# 04_FEATHER-CONNECTION.net
KiCad netlist of a schematic drawn in Altium Designer
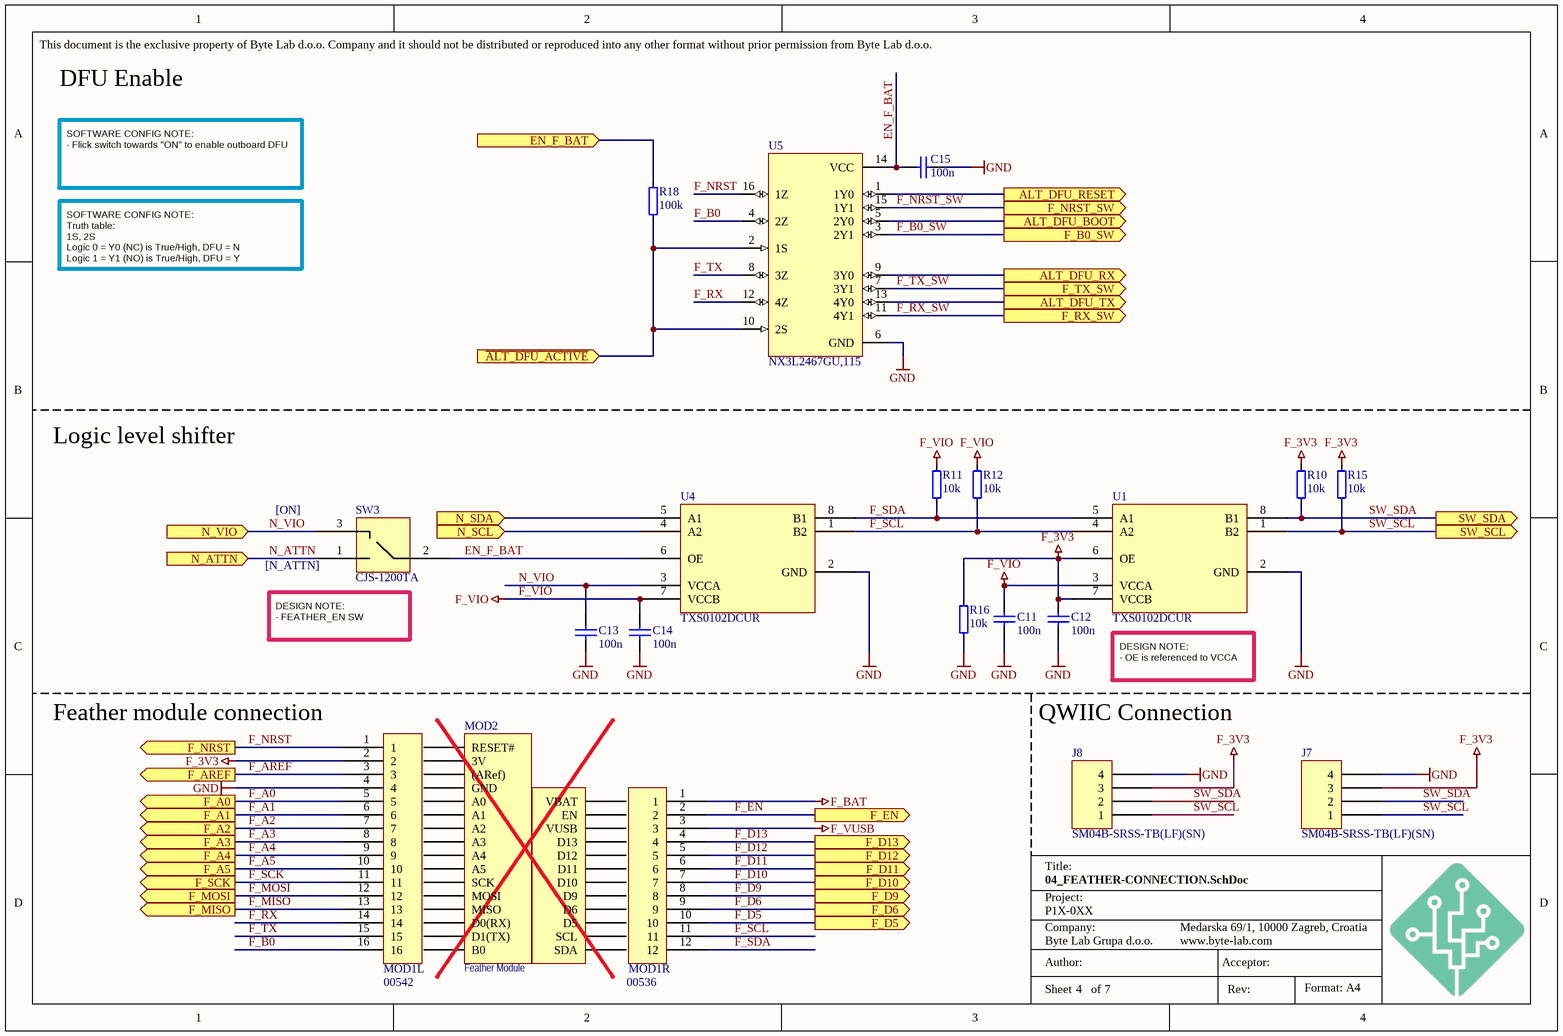
[diagram p0: 04_FEATHER-CONNECTION.SchDoc]

(export (version "E")
  (design (tool "Eeschema 10.0.6"))
  (components
    (comp (ref "C11")
      (value "100n")
      (footprint "C-0402")
      (description "Capacitor ceramic 100n ±10% X7R 16V 0402")
      (fields
        (field (name "BL PART NUMBER") "2000-908")
        (field (name "DRAWN_BY") "Puskar")
        (field (name "CHECKED_BY") "Dodig")
      )
      (libsource (lib "BL_Passive") (part "C0402-100n-16V-X7R"))
    )
    (comp (ref "C12")
      (value "100n")
      (footprint "C-0402")
      (description "Capacitor ceramic 100n ±10% X7R 16V 0402")
      (fields
        (field (name "BL PART NUMBER") "2000-908")
        (field (name "DRAWN_BY") "Puskar")
        (field (name "CHECKED_BY") "Dodig")
      )
      (libsource (lib "BL_Passive") (part "C0402-100n-16V-X7R"))
    )
    (comp (ref "C13")
      (value "100n")
      (footprint "C-0402")
      (description "Capacitor ceramic 100n ±10% X7R 16V 0402")
      (fields
        (field (name "BL PART NUMBER") "2000-908")
        (field (name "DRAWN_BY") "Puskar")
        (field (name "CHECKED_BY") "Dodig")
      )
      (libsource (lib "BL_Passive") (part "C0402-100n-16V-X7R"))
    )
    (comp (ref "C14")
      (value "100n")
      (footprint "C-0402")
      (description "Capacitor ceramic 100n ±10% X7R 16V 0402")
      (fields
        (field (name "BL PART NUMBER") "2000-908")
        (field (name "DRAWN_BY") "Puskar")
        (field (name "CHECKED_BY") "Dodig")
      )
      (libsource (lib "BL_Passive") (part "C0402-100n-16V-X7R"))
    )
    (comp (ref "C15")
      (value "100n")
      (footprint "C-0402")
      (description "Capacitor ceramic 100n ±10% X7R 16V 0402")
      (fields
        (field (name "BL PART NUMBER") "2000-908")
        (field (name "DRAWN_BY") "Puskar")
        (field (name "CHECKED_BY") "Dodig")
      )
      (libsource (lib "BL_Passive") (part "C0402-100n-16V-X7R"))
    )
    (comp (ref "J7")
      (value "SM04B-SRSS-TB(LF)(SN)")
      (footprint "JST SM04B-SRSS-TB")
      (description "CONN HEADER SH 4POS SIDE 1MM TIN")
      (fields
        (field (name "MANUFACTURER") "JST Sales America Inc.")
        (field (name "BL PART NUMBER") "2002-058")
        (field (name "DRAWN_BY") "Blues Wireless")
      )
      (libsource (lib "n21-p2") (part "SM04B-SRSS-TB(LF)(SN)"))
    )
    (comp (ref "J8")
      (value "SM04B-SRSS-TB(LF)(SN)")
      (footprint "JST SM04B-SRSS-TB")
      (description "CONN HEADER SH 4POS SIDE 1MM TIN")
      (fields
        (field (name "MANUFACTURER") "JST Sales America Inc.")
        (field (name "BL PART NUMBER") "2002-058")
        (field (name "DRAWN_BY") "Blues Wireless")
      )
      (libsource (lib "n21-p2") (part "SM04B-SRSS-TB(LF)(SN)"))
    )
    (comp (ref "MOD1L")
      (value "00542")
      (footprint "16PIN_254MM")
      (description "Socket 16-Pin, 0.100 in")
      (fields
        (field (name "MANUFACTURER") "4UCON")
        (field (name "BL PART NUMBER") "2010-423")
        (field (name "DRAWN_BY") "Blues Wireless")
      )
      (libsource (lib "n21-p2") (part "SOCKET_LFB_16"))
    )
    (comp (ref "MOD1R")
      (value "00536")
      (footprint "12PIN_254MM")
      (description "Socket 12-Pin, 0.100 in")
      (fields
        (field (name "MANUFACTURER") "4UCON")
        (field (name "BL PART NUMBER") "2010-424")
        (field (name "DRAWN_BY") "Blues Wireless")
      )
      (libsource (lib "n21-p2") (part "SOCKET_LFB_12"))
    )
    (comp (ref "MOD2")
      (value "Feather Module")
      (footprint "BLUES_WIRELESS_SWAN_2-54_HEADERS")
      (description "Typical Adafruit Feather Pinout")
      (libsource (lib "n21-p2") (part "ADAFRUIT_FEATHER_COMMON_1"))
    )
    (comp (ref "R10")
      (value "10k")
      (footprint "R-0402")
      (description "Resistor 10k ±1% 0402")
      (fields
        (field (name "BL PART NUMBER") "2000-729")
        (field (name "CHECKED_BY") "Dodig")
        (field (name "DRAWN_BY") "Puskar")
      )
      (libsource (lib "BL_Passive") (part "R0402-10k-1"))
    )
    (comp (ref "R11")
      (value "10k")
      (footprint "R-0402")
      (description "Resistor 10k ±1% 0402")
      (fields
        (field (name "BL PART NUMBER") "2000-729")
        (field (name "CHECKED_BY") "Dodig")
        (field (name "DRAWN_BY") "Puskar")
      )
      (libsource (lib "BL_Passive") (part "R0402-10k-1"))
    )
    (comp (ref "R12")
      (value "10k")
      (footprint "R-0402")
      (description "Resistor 10k ±1% 0402")
      (fields
        (field (name "BL PART NUMBER") "2000-729")
        (field (name "CHECKED_BY") "Dodig")
        (field (name "DRAWN_BY") "Puskar")
      )
      (libsource (lib "BL_Passive") (part "R0402-10k-1"))
    )
    (comp (ref "R15")
      (value "10k")
      (footprint "R-0402")
      (description "Resistor 10k ±1% 0402")
      (fields
        (field (name "BL PART NUMBER") "2000-729")
        (field (name "CHECKED_BY") "Dodig")
        (field (name "DRAWN_BY") "Puskar")
      )
      (libsource (lib "BL_Passive") (part "R0402-10k-1"))
    )
    (comp (ref "R16")
      (value "10k")
      (footprint "R-0402")
      (description "Resistor 10k ±1% 0402")
      (fields
        (field (name "BL PART NUMBER") "2000-729")
        (field (name "CHECKED_BY") "Dodig")
        (field (name "DRAWN_BY") "Puskar")
      )
      (libsource (lib "BL_Passive") (part "R0402-10k-1"))
    )
    (comp (ref "R18")
      (value "100k")
      (footprint "R-0402")
      (description "Resistor 100k ±1% 0402")
      (fields
        (field (name "BL PART NUMBER") "2000-727")
        (field (name "CHECKED_BY") "Dodig")
        (field (name "DRAWN_BY") "Puskar")
      )
      (libsource (lib "BL_Passive") (part "R0402-100k-1"))
    )
    (comp (ref "SW3")
      (value "CJS-1200TA")
      (footprint "SW_CJS-1200TA")
      (description "Switch Slide N.O./N.C. SPDT Raised Slide 0.1A 24VDC J-Hook SMD Embossed T/R")
      (fields
        (field (name "MANUFACTURER") "Nidec Copal")
        (field (name "BL PART NUMBER") "2007-456")
        (field (name "DRAWN_BY") "Blues Wireless")
      )
      (libsource (lib "n21-p2") (part "CJS-1200TA"))
    )
    (comp (ref "U1")
      (value "TXS0102DCUR")
      (footprint "SOP50P310X90-8N")
      (fields
        (field (name "MANUFACTURER") "Texas Instruments")
        (field (name "BL PART NUMBER") "2007-455")
        (field (name "DRAWN_BY") "Blues Wireless")
      )
      (libsource (lib "n21-p2") (part "TXS0102DCUR"))
    )
    (comp (ref "U4")
      (value "TXS0102DCUR")
      (footprint "SOP50P310X90-8N")
      (fields
        (field (name "MANUFACTURER") "Texas Instruments")
        (field (name "BL PART NUMBER") "2007-455")
        (field (name "DRAWN_BY") "Blues Wireless")
      )
      (libsource (lib "n21-p2") (part "TXS0102DCUR"))
    )
    (comp (ref "U5")
      (value "NX3L2467GU,115")
      (footprint "BL_Components:QFN40P180X260X55-16N")
      (description "IC ANALOG SWITCH DPDTX2 16XQFN")
      (fields
        (field (name "MANUFACTURER") "NXP")
        (field (name "BL PART NUMBER") "2009-148")
        (field (name "CHECKED_BY") "Duracic")
        (field (name "DRAWN_BY") "Marsic")
      )
      (libsource (lib "BL_Digital") (part "NX3L2467GU,115"))
    )
  )
  (nets
    (net (code "1") (name "/ALT_DFU_BOOT") (class "Default")
      (node (ref "U5") (pin "5") (pinfunction "2Y0_5") (pintype "bidirectional"))
    )
    (net (code "2") (name "/ALT_DFU_RESET") (class "Default")
      (node (ref "U5") (pin "1") (pinfunction "1Y0_1") (pintype "bidirectional"))
    )
    (net (code "3") (name "/ALT_DFU_RX") (class "Default")
      (node (ref "U5") (pin "9") (pinfunction "3Y0_9") (pintype "bidirectional"))
    )
    (net (code "4") (name "/ALT_DFU_TX") (class "Default")
      (node (ref "U5") (pin "13") (pinfunction "4Y0_13") (pintype "bidirectional"))
    )
    (net (code "5") (name "/EN_F_BAT") (class "Default")
      (node (ref "C15") (pin "2") (pinfunction "2_2") (pintype "passive"))
      (node (ref "R18") (pin "2") (pintype "passive"))
      (node (ref "SW3") (pin "2") (pinfunction "2_2") (pintype "passive"))
      (node (ref "U4") (pin "6") (pinfunction "OE_6") (pintype "passive"))
      (node (ref "U5") (pin "14") (pinfunction "VCC_14") (pintype "power_in"))
    )
    (net (code "6") (name "/F_A0") (class "Default")
      (node (ref "MOD1L") (pin "5") (pinfunction "5_5") (pintype "passive"))
    )
    (net (code "7") (name "/F_A1") (class "Default")
      (node (ref "MOD1L") (pin "6") (pinfunction "6_6") (pintype "passive"))
    )
    (net (code "8") (name "/F_A2") (class "Default")
      (node (ref "MOD1L") (pin "7") (pinfunction "7_7") (pintype "passive"))
    )
    (net (code "9") (name "/F_A3") (class "Default")
      (node (ref "MOD1L") (pin "8") (pinfunction "8_8") (pintype "passive"))
    )
    (net (code "10") (name "/F_A4") (class "Default")
      (node (ref "MOD1L") (pin "9") (pinfunction "9_9") (pintype "passive"))
    )
    (net (code "11") (name "/F_A5") (class "Default")
      (node (ref "MOD1L") (pin "10") (pinfunction "10_10") (pintype "passive"))
    )
    (net (code "12") (name "/F_AREF") (class "Default")
      (node (ref "MOD1L") (pin "3") (pinfunction "3_3") (pintype "passive"))
    )
    (net (code "13") (name "/F_B0") (class "Default")
      (node (ref "MOD1L") (pin "16") (pinfunction "16_16") (pintype "passive"))
      (node (ref "U5") (pin "4") (pinfunction "2Z_4") (pintype "bidirectional"))
    )
    (net (code "14") (name "/F_B0_SW") (class "Default")
      (node (ref "U5") (pin "3") (pinfunction "2Y1_3") (pintype "bidirectional"))
    )
    (net (code "15") (name "/F_D5") (class "Default")
      (node (ref "MOD1R") (pin "10") (pinfunction "10_10") (pintype "passive"))
    )
    (net (code "16") (name "/F_D6") (class "Default")
      (node (ref "MOD1R") (pin "9") (pinfunction "9_9") (pintype "passive"))
    )
    (net (code "17") (name "/F_D9") (class "Default")
      (node (ref "MOD1R") (pin "8") (pinfunction "8_8") (pintype "passive"))
    )
    (net (code "18") (name "/F_D10") (class "Default")
      (node (ref "MOD1R") (pin "7") (pinfunction "7_7") (pintype "passive"))
    )
    (net (code "19") (name "/F_D11") (class "Default")
      (node (ref "MOD1R") (pin "6") (pinfunction "6_6") (pintype "passive"))
    )
    (net (code "20") (name "/F_D12") (class "Default")
      (node (ref "MOD1R") (pin "5") (pinfunction "5_5") (pintype "passive"))
    )
    (net (code "21") (name "/F_D13") (class "Default")
      (node (ref "MOD1R") (pin "4") (pinfunction "4_4") (pintype "passive"))
    )
    (net (code "22") (name "/F_EN") (class "Default")
      (node (ref "MOD1R") (pin "2") (pinfunction "2_2") (pintype "passive"))
    )
    (net (code "23") (name "/F_MISO") (class "Default")
      (node (ref "MOD1L") (pin "13") (pinfunction "13_13") (pintype "passive"))
    )
    (net (code "24") (name "/F_MOSI") (class "Default")
      (node (ref "MOD1L") (pin "12") (pinfunction "12_12") (pintype "passive"))
    )
    (net (code "25") (name "/F_NRST") (class "Default")
      (node (ref "MOD1L") (pin "1") (pinfunction "1_1") (pintype "passive"))
      (node (ref "U5") (pin "16") (pinfunction "1Z_16") (pintype "bidirectional"))
    )
    (net (code "26") (name "/F_NRST_SW") (class "Default")
      (node (ref "U5") (pin "15") (pinfunction "1Y1_15") (pintype "bidirectional"))
    )
    (net (code "27") (name "/F_RX") (class "Default")
      (node (ref "MOD1L") (pin "14") (pinfunction "14_14") (pintype "passive"))
      (node (ref "U5") (pin "12") (pinfunction "4Z_12") (pintype "bidirectional"))
    )
    (net (code "28") (name "/F_RX_SW") (class "Default")
      (node (ref "U5") (pin "11") (pinfunction "4Y1_11") (pintype "bidirectional"))
    )
    (net (code "29") (name "/F_SCK") (class "Default")
      (node (ref "MOD1L") (pin "11") (pinfunction "11_11") (pintype "passive"))
    )
    (net (code "30") (name "/F_SCL") (class "Default")
      (node (ref "MOD1R") (pin "11") (pinfunction "11_11") (pintype "passive"))
      (node (ref "R12") (pin "1") (pintype "passive"))
      (node (ref "U1") (pin "4") (pinfunction "A2_4") (pintype "passive"))
      (node (ref "U4") (pin "1") (pinfunction "B2_1") (pintype "passive"))
    )
    (net (code "31") (name "/F_SDA") (class "Default")
      (node (ref "MOD1R") (pin "12") (pinfunction "12_12") (pintype "passive"))
      (node (ref "R11") (pin "1") (pintype "passive"))
      (node (ref "U1") (pin "5") (pinfunction "A1_5") (pintype "passive"))
      (node (ref "U4") (pin "8") (pinfunction "B1_8") (pintype "passive"))
    )
    (net (code "32") (name "/F_TX") (class "Default")
      (node (ref "MOD1L") (pin "15") (pinfunction "15_15") (pintype "passive"))
      (node (ref "U5") (pin "8") (pinfunction "3Z_8") (pintype "bidirectional"))
    )
    (net (code "33") (name "/F_TX_SW") (class "Default")
      (node (ref "U5") (pin "7") (pinfunction "3Y1_7") (pintype "bidirectional"))
    )
    (net (code "34") (name "/N_ATTN") (class "Default")
      (node (ref "SW3") (pin "1") (pinfunction "1_1") (pintype "passive"))
    )
    (net (code "35") (name "/N_SCL") (class "Default")
      (node (ref "U4") (pin "4") (pinfunction "A2_4") (pintype "passive"))
    )
    (net (code "36") (name "/N_SDA") (class "Default")
      (node (ref "U4") (pin "5") (pinfunction "A1_5") (pintype "passive"))
    )
    (net (code "37") (name "/N_VIO") (class "Default")
      (node (ref "C13") (pin "1") (pinfunction "1_1") (pintype "passive"))
      (node (ref "SW3") (pin "3") (pinfunction "3_3") (pintype "passive"))
      (node (ref "U4") (pin "3") (pinfunction "VCCA_3") (pintype "passive"))
    )
    (net (code "38") (name "/SW_SCL") (class "Default")
      (node (ref "J7") (pin "1") (pinfunction "1_1") (pintype "passive"))
      (node (ref "J8") (pin "1") (pinfunction "1_1") (pintype "passive"))
      (node (ref "R15") (pin "1") (pintype "passive"))
      (node (ref "U1") (pin "1") (pinfunction "B2_1") (pintype "passive"))
    )
    (net (code "39") (name "/SW_SDA") (class "Default")
      (node (ref "J7") (pin "2") (pinfunction "2_2") (pintype "passive"))
      (node (ref "J8") (pin "2") (pinfunction "2_2") (pintype "passive"))
      (node (ref "R10") (pin "1") (pintype "passive"))
      (node (ref "U1") (pin "8") (pinfunction "B1_8") (pintype "passive"))
    )
    (net (code "40") (name "/~{ALT_DFU_ACTIVE}") (class "Default")
      (node (ref "R18") (pin "1") (pintype "passive"))
      (node (ref "U5") (pin "10") (pinfunction "2S_10") (pintype "input"))
      (node (ref "U5") (pin "2") (pinfunction "1S_2") (pintype "input"))
    )
    (net (code "41") (name "F_3V3") (class "Default")
      (node (ref "C12") (pin "1") (pinfunction "1_1") (pintype "passive"))
      (node (ref "J7") (pin "3") (pinfunction "3_3") (pintype "passive"))
      (node (ref "J8") (pin "3") (pinfunction "3_3") (pintype "passive"))
      (node (ref "MOD1L") (pin "2") (pinfunction "2_2") (pintype "passive"))
      (node (ref "R10") (pin "2") (pintype "passive"))
      (node (ref "R15") (pin "2") (pintype "passive"))
      (node (ref "R16") (pin "1") (pintype "passive"))
      (node (ref "U1") (pin "6") (pinfunction "OE_6") (pintype "passive"))
      (node (ref "U1") (pin "7") (pinfunction "VCCB_7") (pintype "passive"))
    )
    (net (code "42") (name "F_BAT") (class "Default")
      (node (ref "MOD1R") (pin "1") (pinfunction "1_1") (pintype "passive"))
    )
    (net (code "43") (name "F_VIO") (class "Default")
      (node (ref "C11") (pin "1") (pinfunction "1_1") (pintype "passive"))
      (node (ref "C14") (pin "1") (pinfunction "1_1") (pintype "passive"))
      (node (ref "R11") (pin "2") (pintype "passive"))
      (node (ref "R12") (pin "2") (pintype "passive"))
      (node (ref "U1") (pin "3") (pinfunction "VCCA_3") (pintype "passive"))
      (node (ref "U4") (pin "7") (pinfunction "VCCB_7") (pintype "passive"))
    )
    (net (code "44") (name "F_VUSB") (class "Default")
      (node (ref "MOD1R") (pin "3") (pinfunction "3_3") (pintype "passive"))
    )
    (net (code "45") (name "GND") (class "Default")
      (node (ref "C11") (pin "2") (pinfunction "2_2") (pintype "passive"))
      (node (ref "C12") (pin "2") (pinfunction "2_2") (pintype "passive"))
      (node (ref "C13") (pin "2") (pinfunction "2_2") (pintype "passive"))
      (node (ref "C14") (pin "2") (pinfunction "2_2") (pintype "passive"))
      (node (ref "C15") (pin "1") (pinfunction "1_1") (pintype "passive"))
      (node (ref "J7") (pin "4") (pinfunction "4_4") (pintype "passive"))
      (node (ref "J8") (pin "4") (pinfunction "4_4") (pintype "passive"))
      (node (ref "MOD1L") (pin "4") (pinfunction "4_4") (pintype "passive"))
      (node (ref "R16") (pin "2") (pintype "passive"))
      (node (ref "U1") (pin "2") (pinfunction "GND_2") (pintype "passive"))
      (node (ref "U4") (pin "2") (pinfunction "GND_2") (pintype "passive"))
      (node (ref "U5") (pin "6") (pinfunction "GND_6") (pintype "power_in"))
    )
    (net (code "46") (name "unconnected-(MOD2-(ARef)-Pad3)") (class "Default")
      (node (ref "MOD2") (pin "3") (pinfunction "(ARef)_3") (pintype "passive"))
    )
    (net (code "47") (name "unconnected-(MOD2-3V-Pad2)") (class "Default")
      (node (ref "MOD2") (pin "2") (pinfunction "3V_2") (pintype "passive"))
    )
    (net (code "48") (name "unconnected-(MOD2-A0-Pad5)") (class "Default")
      (node (ref "MOD2") (pin "5") (pinfunction "A0_5") (pintype "passive"))
    )
    (net (code "49") (name "unconnected-(MOD2-A1-Pad6)") (class "Default")
      (node (ref "MOD2") (pin "6") (pinfunction "A1_6") (pintype "passive"))
    )
    (net (code "50") (name "unconnected-(MOD2-A2-Pad7)") (class "Default")
      (node (ref "MOD2") (pin "7") (pinfunction "A2_7") (pintype "passive"))
    )
    (net (code "51") (name "unconnected-(MOD2-A3-Pad8)") (class "Default")
      (node (ref "MOD2") (pin "8") (pinfunction "A3_8") (pintype "passive"))
    )
    (net (code "52") (name "unconnected-(MOD2-A4-Pad9)") (class "Default")
      (node (ref "MOD2") (pin "9") (pinfunction "A4_9") (pintype "passive"))
    )
    (net (code "53") (name "unconnected-(MOD2-A5-Pad10)") (class "Default")
      (node (ref "MOD2") (pin "10") (pinfunction "A5_10") (pintype "passive"))
    )
    (net (code "54") (name "unconnected-(MOD2-B0-Pad16)") (class "Default")
      (node (ref "MOD2") (pin "16") (pinfunction "B0_16") (pintype "passive"))
    )
    (net (code "55") (name "unconnected-(MOD2-D0(RX)-Pad14)") (class "Default")
      (node (ref "MOD2") (pin "14") (pinfunction "D0(RX)_14") (pintype "passive"))
    )
    (net (code "56") (name "unconnected-(MOD2-D1(TX)-Pad15)") (class "Default")
      (node (ref "MOD2") (pin "15") (pinfunction "D1(TX)_15") (pintype "passive"))
    )
    (net (code "57") (name "unconnected-(MOD2-D5-Pad19)") (class "Default")
      (node (ref "MOD2") (pin "19") (pinfunction "D5_19") (pintype "passive"))
    )
    (net (code "58") (name "unconnected-(MOD2-D6-Pad20)") (class "Default")
      (node (ref "MOD2") (pin "20") (pinfunction "D6_20") (pintype "passive"))
    )
    (net (code "59") (name "unconnected-(MOD2-D9-Pad21)") (class "Default")
      (node (ref "MOD2") (pin "21") (pinfunction "D9_21") (pintype "passive"))
    )
    (net (code "60") (name "unconnected-(MOD2-D10-Pad22)") (class "Default")
      (node (ref "MOD2") (pin "22") (pinfunction "D10_22") (pintype "passive"))
    )
    (net (code "61") (name "unconnected-(MOD2-D11-Pad23)") (class "Default")
      (node (ref "MOD2") (pin "23") (pinfunction "D11_23") (pintype "passive"))
    )
    (net (code "62") (name "unconnected-(MOD2-D12-Pad24)") (class "Default")
      (node (ref "MOD2") (pin "24") (pinfunction "D12_24") (pintype "passive"))
    )
    (net (code "63") (name "unconnected-(MOD2-D13-Pad25)") (class "Default")
      (node (ref "MOD2") (pin "25") (pinfunction "D13_25") (pintype "passive"))
    )
    (net (code "64") (name "unconnected-(MOD2-EN-Pad27)") (class "Default")
      (node (ref "MOD2") (pin "27") (pinfunction "EN_27") (pintype "passive"))
    )
    (net (code "65") (name "unconnected-(MOD2-GND-Pad4)") (class "Default")
      (node (ref "MOD2") (pin "4") (pinfunction "GND_4") (pintype "passive"))
    )
    (net (code "66") (name "unconnected-(MOD2-MISO-Pad13)") (class "Default")
      (node (ref "MOD2") (pin "13") (pinfunction "MISO_13") (pintype "passive"))
    )
    (net (code "67") (name "unconnected-(MOD2-MOSI-Pad12)") (class "Default")
      (node (ref "MOD2") (pin "12") (pinfunction "MOSI_12") (pintype "passive"))
    )
    (net (code "68") (name "unconnected-(MOD2-RESET#-Pad1)") (class "Default")
      (node (ref "MOD2") (pin "1") (pinfunction "RESET#_1") (pintype "passive"))
    )
    (net (code "69") (name "unconnected-(MOD2-SCK-Pad11)") (class "Default")
      (node (ref "MOD2") (pin "11") (pinfunction "SCK_11") (pintype "passive"))
    )
    (net (code "70") (name "unconnected-(MOD2-SCL-Pad18)") (class "Default")
      (node (ref "MOD2") (pin "18") (pinfunction "SCL_18") (pintype "passive"))
    )
    (net (code "71") (name "unconnected-(MOD2-SDA-Pad17)") (class "Default")
      (node (ref "MOD2") (pin "17") (pinfunction "SDA_17") (pintype "passive"))
    )
    (net (code "72") (name "unconnected-(MOD2-VBAT-Pad28)") (class "Default")
      (node (ref "MOD2") (pin "28") (pinfunction "VBAT_28") (pintype "passive"))
    )
    (net (code "73") (name "unconnected-(MOD2-VUSB-Pad26)") (class "Default")
      (node (ref "MOD2") (pin "26") (pinfunction "VUSB_26") (pintype "passive"))
    )
  )
)
